# RHC12.net
KiCad netlist of a schematic drawn in Altium Designer
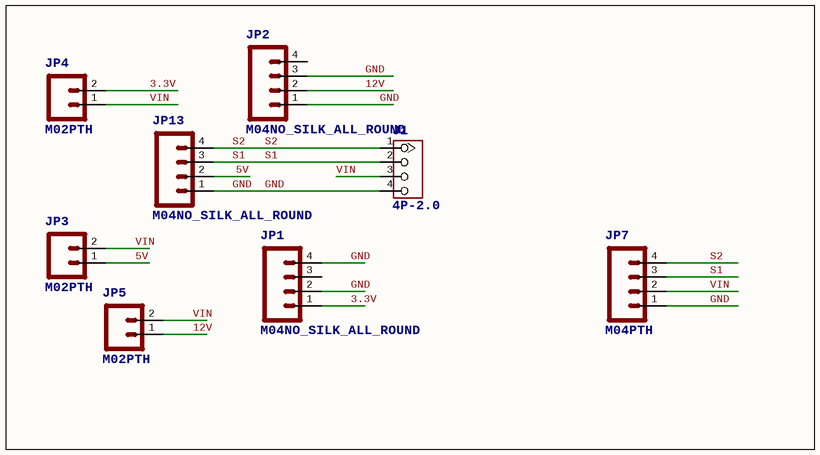
[diagram p0: RHC12.SchDoc]

(export (version "E")
  (design (tool "Eeschema 10.0.6"))
  (components
    (comp (ref "J1")
      (value "4P-2.0")
      (footprint "HW4-2.0")
      (description "320110033")
      (libsource (lib "Seeed-OPL-Connector") (part "GROVE-CONNECTOR-DIP(4P-2.0)"))
    )
    (comp (ref "JP1")
      (value "M04NO_SILK_ALL_ROUND")
      (footprint "1X04_NO_SILK_ALL_ROUND")
      (libsource (lib "SparkFun-Connectors") (part "M04NO_SILK_ALL_ROUND"))
    )
    (comp (ref "JP2")
      (value "M04NO_SILK_ALL_ROUND")
      (footprint "1X04_NO_SILK_ALL_ROUND")
      (libsource (lib "SparkFun-Connectors") (part "M04NO_SILK_ALL_ROUND"))
    )
    (comp (ref "JP3")
      (value "M02PTH")
      (footprint "1X02")
      (libsource (lib "SparkFun-Connectors") (part "M02PTH"))
    )
    (comp (ref "JP4")
      (value "M02PTH")
      (footprint "1X02")
      (libsource (lib "SparkFun-Connectors") (part "M02PTH"))
    )
    (comp (ref "JP5")
      (value "M02PTH")
      (footprint "1X02")
      (libsource (lib "SparkFun-Connectors") (part "M02PTH"))
    )
    (comp (ref "JP7")
      (value "M04PTH")
      (footprint "1X04")
      (libsource (lib "SparkFun-Connectors") (part "M04PTH"))
    )
    (comp (ref "JP13")
      (value "M04NO_SILK_ALL_ROUND")
      (footprint "1X04_NO_SILK_ALL_ROUND")
      (libsource (lib "SparkFun-Connectors") (part "M04NO_SILK_ALL_ROUND"))
    )
  )
  (nets
    (net (code "1") (name "/3.3V") (class "Default")
      (node (ref "JP1") (pin "1") (pinfunction "1_1") (pintype "passive"))
      (node (ref "JP4") (pin "2") (pinfunction "2_2") (pintype "passive"))
    )
    (net (code "2") (name "/5V") (class "Default")
      (node (ref "JP13") (pin "2") (pinfunction "2_2") (pintype "passive"))
      (node (ref "JP3") (pin "1") (pinfunction "1_1") (pintype "passive"))
    )
    (net (code "3") (name "/12V") (class "Default")
      (node (ref "JP2") (pin "2") (pinfunction "2_2") (pintype "passive"))
      (node (ref "JP5") (pin "1") (pinfunction "1_1") (pintype "passive"))
    )
    (net (code "4") (name "/GND") (class "Default")
      (node (ref "J1") (pin "4") (pinfunction "4_4") (pintype "passive"))
      (node (ref "JP1") (pin "2") (pinfunction "2_2") (pintype "passive"))
      (node (ref "JP1") (pin "4") (pinfunction "4_4") (pintype "passive"))
      (node (ref "JP13") (pin "1") (pinfunction "1_1") (pintype "passive"))
      (node (ref "JP2") (pin "1") (pinfunction "1_1") (pintype "passive"))
      (node (ref "JP2") (pin "3") (pinfunction "3_3") (pintype "passive"))
      (node (ref "JP7") (pin "1") (pinfunction "1_1") (pintype "passive"))
    )
    (net (code "5") (name "/S1") (class "Default")
      (node (ref "J1") (pin "2") (pinfunction "2_2") (pintype "passive"))
      (node (ref "JP13") (pin "3") (pinfunction "3_3") (pintype "passive"))
      (node (ref "JP7") (pin "3") (pinfunction "3_3") (pintype "passive"))
    )
    (net (code "6") (name "/S2") (class "Default")
      (node (ref "J1") (pin "1") (pinfunction "1_1") (pintype "passive"))
      (node (ref "JP13") (pin "4") (pinfunction "4_4") (pintype "passive"))
      (node (ref "JP7") (pin "4") (pinfunction "4_4") (pintype "passive"))
    )
    (net (code "7") (name "/VIN") (class "Default")
      (node (ref "J1") (pin "3") (pinfunction "3_3") (pintype "passive"))
      (node (ref "JP3") (pin "2") (pinfunction "2_2") (pintype "passive"))
      (node (ref "JP4") (pin "1") (pinfunction "1_1") (pintype "passive"))
      (node (ref "JP5") (pin "2") (pinfunction "2_2") (pintype "passive"))
      (node (ref "JP7") (pin "2") (pinfunction "2_2") (pintype "passive"))
    )
    (net (code "8") (name "unconnected-(JP1-Pad3)") (class "Default")
      (node (ref "JP1") (pin "3") (pinfunction "3_3") (pintype "passive"))
    )
    (net (code "9") (name "unconnected-(JP2-Pad4)") (class "Default")
      (node (ref "JP2") (pin "4") (pinfunction "4_4") (pintype "passive"))
    )
  )
)
